# Leddriverboard.net
KiCad netlist of a schematic drawn in EAGLE
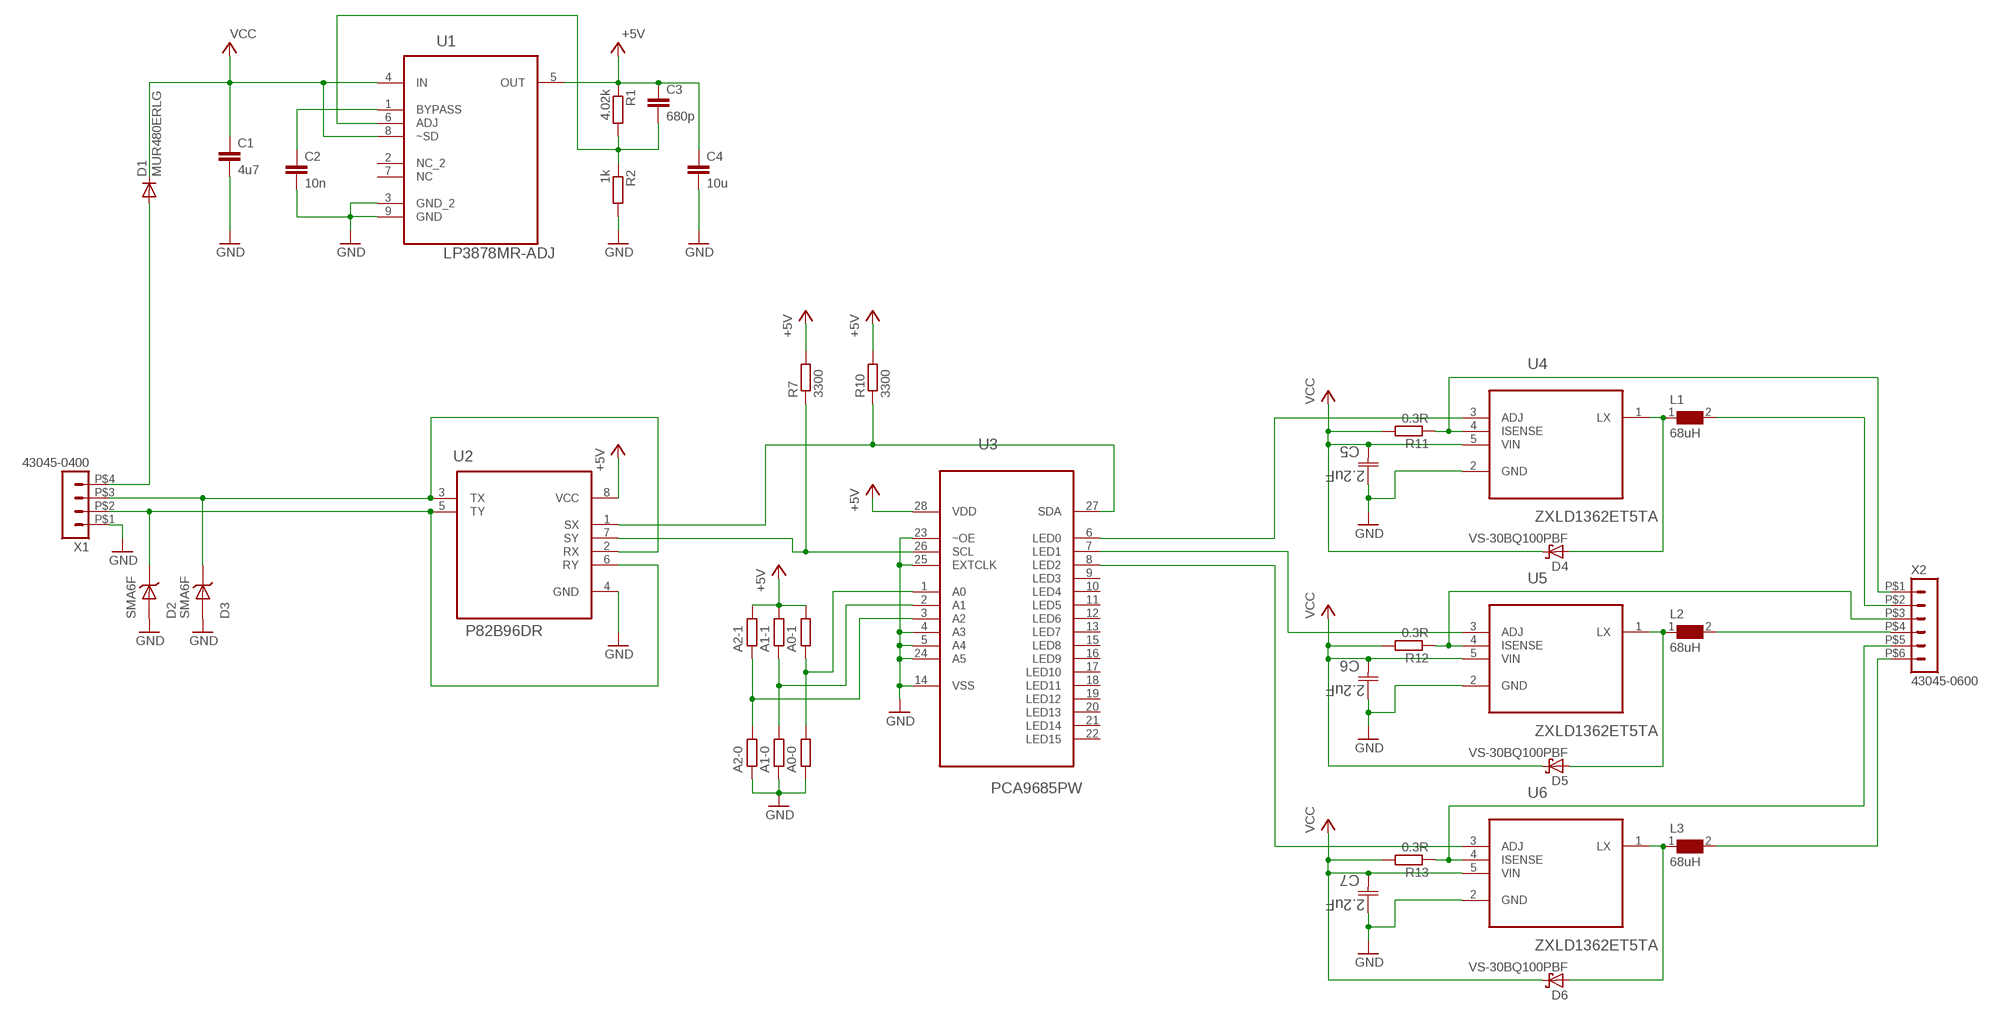
[diagram p0: schematic, sheet 1]

(export (version "E")
  (design (tool "Eeschema 10.0.6"))
  (components
    (comp (ref "C1")
      (value "4u7")
      (footprint "eagle-import:C0805")
      (libsource (lib "eagle-import") (part "C-EUC0805"))
    )
    (comp (ref "C2")
      (value "10n")
      (footprint "eagle-import:C0805")
      (libsource (lib "eagle-import") (part "C-EUC0805"))
    )
    (comp (ref "C3")
      (value "680p")
      (footprint "eagle-import:C0805")
      (libsource (lib "eagle-import") (part "C-EUC0805"))
    )
    (comp (ref "C4")
      (value "10u")
      (footprint "eagle-import:C0805")
      (libsource (lib "eagle-import") (part "C-EUC0805"))
    )
    (comp (ref "C5")
      (value "2.2uF")
      (footprint "eagle-import:CAPC2013X152N")
      (fields (field (name "MPN") "08053C225KAT2A") (field (name "TOLERANCE") "±10%"))
      (libsource (lib "eagle-import") (part "08053C225KAT2A"))
    )
    (comp (ref "C6")
      (value "2.2uF")
      (footprint "eagle-import:CAPC2013X152N")
      (fields (field (name "MPN") "08053C225KAT2A") (field (name "TOLERANCE") "±10%"))
      (libsource (lib "eagle-import") (part "08053C225KAT2A"))
    )
    (comp (ref "C7")
      (value "2.2uF")
      (footprint "eagle-import:CAPC2013X152N")
      (fields (field (name "MPN") "08053C225KAT2A") (field (name "TOLERANCE") "±10%"))
      (libsource (lib "eagle-import") (part "08053C225KAT2A"))
    )
    (comp (ref "D1")
      (value "MUR480ERLG")
      (footprint "eagle-import:DO41-10")
      (libsource (lib "eagle-import") (part "MUR150RL"))
    )
    (comp (ref "D2")
      (value "SMA6F")
      (footprint "eagle-import:DO-221AC")
      (libsource (lib "eagle-import") (part "SMA6F"))
    )
    (comp (ref "D3")
      (value "SMA6F")
      (footprint "eagle-import:DO-221AC")
      (libsource (lib "eagle-import") (part "SMA6F"))
    )
    (comp (ref "D4")
      (value "VS-30BQ100PBF")
      (footprint "eagle-import:DO-214AB")
      (libsource (lib "eagle-import") (part "VS-30BQ100PBF"))
    )
    (comp (ref "D5")
      (value "VS-30BQ100PBF")
      (footprint "eagle-import:DO-214AB")
      (libsource (lib "eagle-import") (part "VS-30BQ100PBF"))
    )
    (comp (ref "D6")
      (value "VS-30BQ100PBF")
      (footprint "eagle-import:DO-214AB")
      (libsource (lib "eagle-import") (part "VS-30BQ100PBF"))
    )
    (comp (ref "L1")
      (value "68uH")
      (footprint "eagle-import:L")
      (fields (field (name "MPN") "74456168"))
      (libsource (lib "eagle-import") (part "WE-PD4_L-74456168"))
    )
    (comp (ref "L2")
      (value "68uH")
      (footprint "eagle-import:L")
      (fields (field (name "MPN") "74456168"))
      (libsource (lib "eagle-import") (part "WE-PD4_L-74456168"))
    )
    (comp (ref "L3")
      (value "68uH")
      (footprint "eagle-import:L")
      (fields (field (name "MPN") "74456168"))
      (libsource (lib "eagle-import") (part "WE-PD4_L-74456168"))
    )
    (comp (ref "R1")
      (value "4.02k")
      (footprint "eagle-import:R0603")
      (libsource (lib "eagle-import") (part "resistor_R-EU_R0603"))
    )
    (comp (ref "R2")
      (value "1k")
      (footprint "eagle-import:R0603")
      (libsource (lib "eagle-import") (part "resistor_R-EU_R0603"))
    )
    (comp (ref "R3")
      (value "A2-1")
      (footprint "eagle-import:R0402")
      (libsource (lib "eagle-import") (part "resistor_R-EU_R0402"))
    )
    (comp (ref "R4")
      (value "A2-0")
      (footprint "eagle-import:R0402")
      (libsource (lib "eagle-import") (part "resistor_R-EU_R0402"))
    )
    (comp (ref "R5")
      (value "A1-1")
      (footprint "eagle-import:R0402")
      (libsource (lib "eagle-import") (part "resistor_R-EU_R0402"))
    )
    (comp (ref "R6")
      (value "A1-0")
      (footprint "eagle-import:R0402")
      (libsource (lib "eagle-import") (part "resistor_R-EU_R0402"))
    )
    (comp (ref "R7")
      (value "3300")
      (footprint "eagle-import:0204_7")
      (libsource (lib "eagle-import") (part "R-EU_0204/7"))
    )
    (comp (ref "R8")
      (value "A0-1")
      (footprint "eagle-import:R0402")
      (libsource (lib "eagle-import") (part "resistor_R-EU_R0402"))
    )
    (comp (ref "R9")
      (value "A0-0")
      (footprint "eagle-import:R0402")
      (libsource (lib "eagle-import") (part "resistor_R-EU_R0402"))
    )
    (comp (ref "R10")
      (value "3300")
      (footprint "eagle-import:0204_7")
      (libsource (lib "eagle-import") (part "R-EU_0204/7"))
    )
    (comp (ref "R11")
      (value "0.3R")
      (footprint "eagle-import:R0603")
      (libsource (lib "eagle-import") (part "resistor_R-EU_R0603"))
    )
    (comp (ref "R12")
      (value "0.3R")
      (footprint "eagle-import:R0603")
      (libsource (lib "eagle-import") (part "resistor_R-EU_R0603"))
    )
    (comp (ref "R13")
      (value "0.3R")
      (footprint "eagle-import:R0603")
      (libsource (lib "eagle-import") (part "resistor_R-EU_R0603"))
    )
    (comp (ref "U1")
      (value "LP3878MR-ADJ")
      (footprint "eagle-import:SOIC127P600X168-8N")
      (libsource (lib "eagle-import") (part "LP3878MR-ADJ"))
    )
    (comp (ref "U2")
      (value "P82B96DR")
      (footprint "eagle-import:SOIC127P600X175-8N")
      (libsource (lib "eagle-import") (part "P82B96DR"))
    )
    (comp (ref "U3")
      (value "PCA9685PW")
      (footprint "eagle-import:SOP65P640X110-28N")
      (libsource (lib "eagle-import") (part "PCA9685PW"))
    )
    (comp (ref "U4")
      (value "ZXLD1362ET5TA")
      (footprint "eagle-import:SOT95P270X145-5N")
      (libsource (lib "eagle-import") (part "ZXLD1362ET5TA"))
    )
    (comp (ref "U5")
      (value "ZXLD1362ET5TA")
      (footprint "eagle-import:SOT95P270X145-5N")
      (libsource (lib "eagle-import") (part "ZXLD1362ET5TA"))
    )
    (comp (ref "U6")
      (value "ZXLD1362ET5TA")
      (footprint "eagle-import:SOT95P270X145-5N")
      (libsource (lib "eagle-import") (part "ZXLD1362ET5TA"))
    )
    (comp (ref "X1")
      (value "43045-0400")
      (footprint "eagle-import:43045-0400")
      (libsource (lib "eagle-import") (part "HEADER_POS4_?43045-0401"))
    )
    (comp (ref "X2")
      (value "43045-0600")
      (footprint "eagle-import:43045-0600")
      (libsource (lib "eagle-import") (part "HEADER_POS6_?43045-0600"))
    )
  )
  (nets
    (net (code "1") (name "+5V") (class "Default")
      (node (ref "C3") (pin "1") (pinfunction "1_1") (pintype "passive"))
      (node (ref "C4") (pin "1") (pinfunction "1_1") (pintype "passive"))
      (node (ref "R1") (pin "1") (pinfunction "1_1") (pintype "passive"))
      (node (ref "R10") (pin "2") (pinfunction "2_2") (pintype "passive"))
      (node (ref "R3") (pin "2") (pinfunction "2_2") (pintype "passive"))
      (node (ref "R5") (pin "2") (pinfunction "2_2") (pintype "passive"))
      (node (ref "R7") (pin "2") (pinfunction "2_2") (pintype "passive"))
      (node (ref "R8") (pin "2") (pinfunction "2_2") (pintype "passive"))
      (node (ref "U1") (pin "5") (pinfunction "OUT_5") (pintype "output"))
      (node (ref "U2") (pin "8") (pinfunction "VCC_8") (pintype "power_in"))
      (node (ref "U3") (pin "28") (pinfunction "VDD_28") (pintype "power_in"))
    )
    (net (code "2") (name "GND") (class "Default")
      (node (ref "C1") (pin "2") (pinfunction "2_2") (pintype "passive"))
      (node (ref "C2") (pin "2") (pinfunction "2_2") (pintype "passive"))
      (node (ref "C4") (pin "2") (pinfunction "2_2") (pintype "passive"))
      (node (ref "C5") (pin "1") (pinfunction "C1_1") (pintype "passive"))
      (node (ref "C6") (pin "1") (pinfunction "C1_1") (pintype "passive"))
      (node (ref "C7") (pin "1") (pinfunction "C1_1") (pintype "passive"))
      (node (ref "D2") (pin "AN") (pinfunction "AN_AN") (pintype "bidirectional"))
      (node (ref "D3") (pin "AN") (pinfunction "AN_AN") (pintype "bidirectional"))
      (node (ref "R2") (pin "2") (pinfunction "2_2") (pintype "passive"))
      (node (ref "R4") (pin "1") (pinfunction "1_1") (pintype "passive"))
      (node (ref "R6") (pin "1") (pinfunction "1_1") (pintype "passive"))
      (node (ref "R9") (pin "1") (pinfunction "1_1") (pintype "passive"))
      (node (ref "U1") (pin "3") (pinfunction "GND_2_3") (pintype "passive"))
      (node (ref "U1") (pin "9") (pinfunction "GND_9") (pintype "passive"))
      (node (ref "U2") (pin "4") (pinfunction "GND_4") (pintype "passive"))
      (node (ref "U3") (pin "14") (pinfunction "VSS_14") (pintype "passive"))
      (node (ref "U3") (pin "23") (pinfunction "~{OE}_23") (pintype "input"))
      (node (ref "U3") (pin "24") (pinfunction "A5_24") (pintype "input"))
      (node (ref "U3") (pin "25") (pinfunction "EXTCLK_25") (pintype "input"))
      (node (ref "U3") (pin "4") (pinfunction "A3_4") (pintype "input"))
      (node (ref "U3") (pin "5") (pinfunction "A4_5") (pintype "input"))
      (node (ref "U4") (pin "2") (pinfunction "GND_2") (pintype "passive"))
      (node (ref "U5") (pin "2") (pinfunction "GND_2") (pintype "passive"))
      (node (ref "U6") (pin "2") (pinfunction "GND_2") (pintype "passive"))
      (node (ref "X1") (pin "P$1") (pinfunction "1_P$1") (pintype "passive"))
    )
    (net (code "3") (name "Net-(U1-ADJ)") (class "Default")
      (node (ref "C3") (pin "2") (pinfunction "2_2") (pintype "passive"))
      (node (ref "R1") (pin "2") (pinfunction "2_2") (pintype "passive"))
      (node (ref "R2") (pin "1") (pinfunction "1_1") (pintype "passive"))
      (node (ref "U1") (pin "6") (pinfunction "ADJ_6") (pintype "passive"))
    )
    (net (code "4") (name "Net-(U1-BYPASS)") (class "Default")
      (node (ref "C2") (pin "1") (pinfunction "1_1") (pintype "passive"))
      (node (ref "U1") (pin "1") (pinfunction "BYPASS_1") (pintype "passive"))
    )
    (net (code "5") (name "Net-(U2-RX)") (class "Default")
      (node (ref "D3") (pin "KAT") (pinfunction "KAT_KAT") (pintype "bidirectional"))
      (node (ref "U2") (pin "2") (pinfunction "RX_2") (pintype "input"))
      (node (ref "U2") (pin "3") (pinfunction "TX_3") (pintype "output"))
      (node (ref "X1") (pin "P$3") (pinfunction "3_P$3") (pintype "passive"))
    )
    (net (code "6") (name "Net-(U2-RY)") (class "Default")
      (node (ref "D2") (pin "KAT") (pinfunction "KAT_KAT") (pintype "bidirectional"))
      (node (ref "U2") (pin "5") (pinfunction "TY_5") (pintype "output"))
      (node (ref "U2") (pin "6") (pinfunction "RY_6") (pintype "input"))
      (node (ref "X1") (pin "P$2") (pinfunction "2_P$2") (pintype "passive"))
    )
    (net (code "7") (name "Net-(U2-SX)") (class "Default")
      (node (ref "R10") (pin "1") (pinfunction "1_1") (pintype "passive"))
      (node (ref "U2") (pin "1") (pinfunction "SX_1") (pintype "input"))
      (node (ref "U3") (pin "27") (pinfunction "SDA_27") (pintype "bidirectional"))
    )
    (net (code "8") (name "Net-(U2-SY)") (class "Default")
      (node (ref "R7") (pin "1") (pinfunction "1_1") (pintype "passive"))
      (node (ref "U2") (pin "7") (pinfunction "SY_7") (pintype "input"))
      (node (ref "U3") (pin "26") (pinfunction "SCL_26") (pintype "input"))
    )
    (net (code "9") (name "Net-(U3-A0)") (class "Default")
      (node (ref "R8") (pin "1") (pinfunction "1_1") (pintype "passive"))
      (node (ref "R9") (pin "2") (pinfunction "2_2") (pintype "passive"))
      (node (ref "U3") (pin "1") (pinfunction "A0_1") (pintype "input"))
    )
    (net (code "10") (name "Net-(U3-A1)") (class "Default")
      (node (ref "R5") (pin "1") (pinfunction "1_1") (pintype "passive"))
      (node (ref "R6") (pin "2") (pinfunction "2_2") (pintype "passive"))
      (node (ref "U3") (pin "2") (pinfunction "A1_2") (pintype "input"))
    )
    (net (code "11") (name "Net-(U3-A2)") (class "Default")
      (node (ref "R3") (pin "1") (pinfunction "1_1") (pintype "passive"))
      (node (ref "R4") (pin "2") (pinfunction "2_2") (pintype "passive"))
      (node (ref "U3") (pin "3") (pinfunction "A2_3") (pintype "input"))
    )
    (net (code "12") (name "Net-(U3-LED0)") (class "Default")
      (node (ref "U3") (pin "6") (pinfunction "LED0_6") (pintype "output"))
      (node (ref "U4") (pin "3") (pinfunction "ADJ_3") (pintype "input"))
    )
    (net (code "13") (name "Net-(U3-LED1)") (class "Default")
      (node (ref "U3") (pin "7") (pinfunction "LED1_7") (pintype "output"))
      (node (ref "U5") (pin "3") (pinfunction "ADJ_3") (pintype "input"))
    )
    (net (code "14") (name "Net-(U3-LED2)") (class "Default")
      (node (ref "U3") (pin "8") (pinfunction "LED2_8") (pintype "output"))
      (node (ref "U6") (pin "3") (pinfunction "ADJ_3") (pintype "input"))
    )
    (net (code "15") (name "Net-(U4-ISENSE)") (class "Default")
      (node (ref "R11") (pin "1") (pinfunction "1_1") (pintype "passive"))
      (node (ref "U4") (pin "4") (pinfunction "ISENSE_4") (pintype "input"))
      (node (ref "X2") (pin "P$1") (pinfunction "1_P$1") (pintype "passive"))
    )
    (net (code "16") (name "Net-(U4-LX)") (class "Default")
      (node (ref "D4") (pin "A") (pinfunction "A_A") (pintype "passive"))
      (node (ref "L1") (pin "1") (pinfunction "1_1") (pintype "passive"))
      (node (ref "U4") (pin "1") (pinfunction "LX_1") (pintype "output"))
    )
    (net (code "17") (name "Net-(U5-ISENSE)") (class "Default")
      (node (ref "R12") (pin "1") (pinfunction "1_1") (pintype "passive"))
      (node (ref "U5") (pin "4") (pinfunction "ISENSE_4") (pintype "input"))
      (node (ref "X2") (pin "P$3") (pinfunction "3_P$3") (pintype "passive"))
    )
    (net (code "18") (name "Net-(U5-LX)") (class "Default")
      (node (ref "D5") (pin "A") (pinfunction "A_A") (pintype "passive"))
      (node (ref "L2") (pin "1") (pinfunction "1_1") (pintype "passive"))
      (node (ref "U5") (pin "1") (pinfunction "LX_1") (pintype "output"))
    )
    (net (code "19") (name "Net-(U6-ISENSE)") (class "Default")
      (node (ref "R13") (pin "1") (pinfunction "1_1") (pintype "passive"))
      (node (ref "U6") (pin "4") (pinfunction "ISENSE_4") (pintype "input"))
      (node (ref "X2") (pin "P$5") (pinfunction "5_P$5") (pintype "passive"))
    )
    (net (code "20") (name "Net-(U6-LX)") (class "Default")
      (node (ref "D6") (pin "A") (pinfunction "A_A") (pintype "passive"))
      (node (ref "L3") (pin "1") (pinfunction "1_1") (pintype "passive"))
      (node (ref "U6") (pin "1") (pinfunction "LX_1") (pintype "output"))
    )
    (net (code "21") (name "Net-(X1-4)") (class "Default")
      (node (ref "D1") (pin "A") (pinfunction "A_A") (pintype "passive"))
      (node (ref "X1") (pin "P$4") (pinfunction "4_P$4") (pintype "passive"))
    )
    (net (code "22") (name "Net-(X2-2)") (class "Default")
      (node (ref "L1") (pin "2") (pinfunction "2_2") (pintype "passive"))
      (node (ref "X2") (pin "P$2") (pinfunction "2_P$2") (pintype "passive"))
    )
    (net (code "23") (name "Net-(X2-4)") (class "Default")
      (node (ref "L2") (pin "2") (pinfunction "2_2") (pintype "passive"))
      (node (ref "X2") (pin "P$4") (pinfunction "4_P$4") (pintype "passive"))
    )
    (net (code "24") (name "Net-(X2-6)") (class "Default")
      (node (ref "L3") (pin "2") (pinfunction "2_2") (pintype "passive"))
      (node (ref "X2") (pin "P$6") (pinfunction "6_P$6") (pintype "passive"))
    )
    (net (code "25") (name "VCC") (class "Default")
      (node (ref "C1") (pin "1") (pinfunction "1_1") (pintype "passive"))
      (node (ref "C5") (pin "2") (pinfunction "C2_2") (pintype "passive"))
      (node (ref "C6") (pin "2") (pinfunction "C2_2") (pintype "passive"))
      (node (ref "C7") (pin "2") (pinfunction "C2_2") (pintype "passive"))
      (node (ref "D1") (pin "C") (pinfunction "C_C") (pintype "passive"))
      (node (ref "D4") (pin "K") (pinfunction "C_K") (pintype "passive"))
      (node (ref "D5") (pin "K") (pinfunction "C_K") (pintype "passive"))
      (node (ref "D6") (pin "K") (pinfunction "C_K") (pintype "passive"))
      (node (ref "R11") (pin "2") (pinfunction "2_2") (pintype "passive"))
      (node (ref "R12") (pin "2") (pinfunction "2_2") (pintype "passive"))
      (node (ref "R13") (pin "2") (pinfunction "2_2") (pintype "passive"))
      (node (ref "U1") (pin "4") (pinfunction "IN_4") (pintype "input"))
      (node (ref "U1") (pin "8") (pinfunction "~{SD}_8") (pintype "passive"))
      (node (ref "U4") (pin "5") (pinfunction "VIN_5") (pintype "input"))
      (node (ref "U5") (pin "5") (pinfunction "VIN_5") (pintype "input"))
      (node (ref "U6") (pin "5") (pinfunction "VIN_5") (pintype "input"))
    )
    (net (code "26") (name "unconnected-(U1-NC-Pad7)") (class "Default")
      (node (ref "U1") (pin "7") (pinfunction "NC_7") (pintype "no_connect"))
    )
    (net (code "27") (name "unconnected-(U1-NC_2-Pad2)") (class "Default")
      (node (ref "U1") (pin "2") (pinfunction "NC_2_2") (pintype "no_connect"))
    )
    (net (code "28") (name "unconnected-(U3-LED3-Pad9)") (class "Default")
      (node (ref "U3") (pin "9") (pinfunction "LED3_9") (pintype "output"))
    )
    (net (code "29") (name "unconnected-(U3-LED4-Pad10)") (class "Default")
      (node (ref "U3") (pin "10") (pinfunction "LED4_10") (pintype "output"))
    )
    (net (code "30") (name "unconnected-(U3-LED5-Pad11)") (class "Default")
      (node (ref "U3") (pin "11") (pinfunction "LED5_11") (pintype "output"))
    )
    (net (code "31") (name "unconnected-(U3-LED6-Pad12)") (class "Default")
      (node (ref "U3") (pin "12") (pinfunction "LED6_12") (pintype "output"))
    )
    (net (code "32") (name "unconnected-(U3-LED7-Pad13)") (class "Default")
      (node (ref "U3") (pin "13") (pinfunction "LED7_13") (pintype "output"))
    )
    (net (code "33") (name "unconnected-(U3-LED8-Pad15)") (class "Default")
      (node (ref "U3") (pin "15") (pinfunction "LED8_15") (pintype "output"))
    )
    (net (code "34") (name "unconnected-(U3-LED9-Pad16)") (class "Default")
      (node (ref "U3") (pin "16") (pinfunction "LED9_16") (pintype "output"))
    )
    (net (code "35") (name "unconnected-(U3-LED10-Pad17)") (class "Default")
      (node (ref "U3") (pin "17") (pinfunction "LED10_17") (pintype "output"))
    )
    (net (code "36") (name "unconnected-(U3-LED11-Pad18)") (class "Default")
      (node (ref "U3") (pin "18") (pinfunction "LED11_18") (pintype "output"))
    )
    (net (code "37") (name "unconnected-(U3-LED12-Pad19)") (class "Default")
      (node (ref "U3") (pin "19") (pinfunction "LED12_19") (pintype "output"))
    )
    (net (code "38") (name "unconnected-(U3-LED13-Pad20)") (class "Default")
      (node (ref "U3") (pin "20") (pinfunction "LED13_20") (pintype "output"))
    )
    (net (code "39") (name "unconnected-(U3-LED14-Pad21)") (class "Default")
      (node (ref "U3") (pin "21") (pinfunction "LED14_21") (pintype "output"))
    )
    (net (code "40") (name "unconnected-(U3-LED15-Pad22)") (class "Default")
      (node (ref "U3") (pin "22") (pinfunction "LED15_22") (pintype "output"))
    )
  )
)
